# Adafruit_I2C_SPI_LCD_STEMMA_backpack.net
KiCad netlist of a schematic drawn in EAGLE
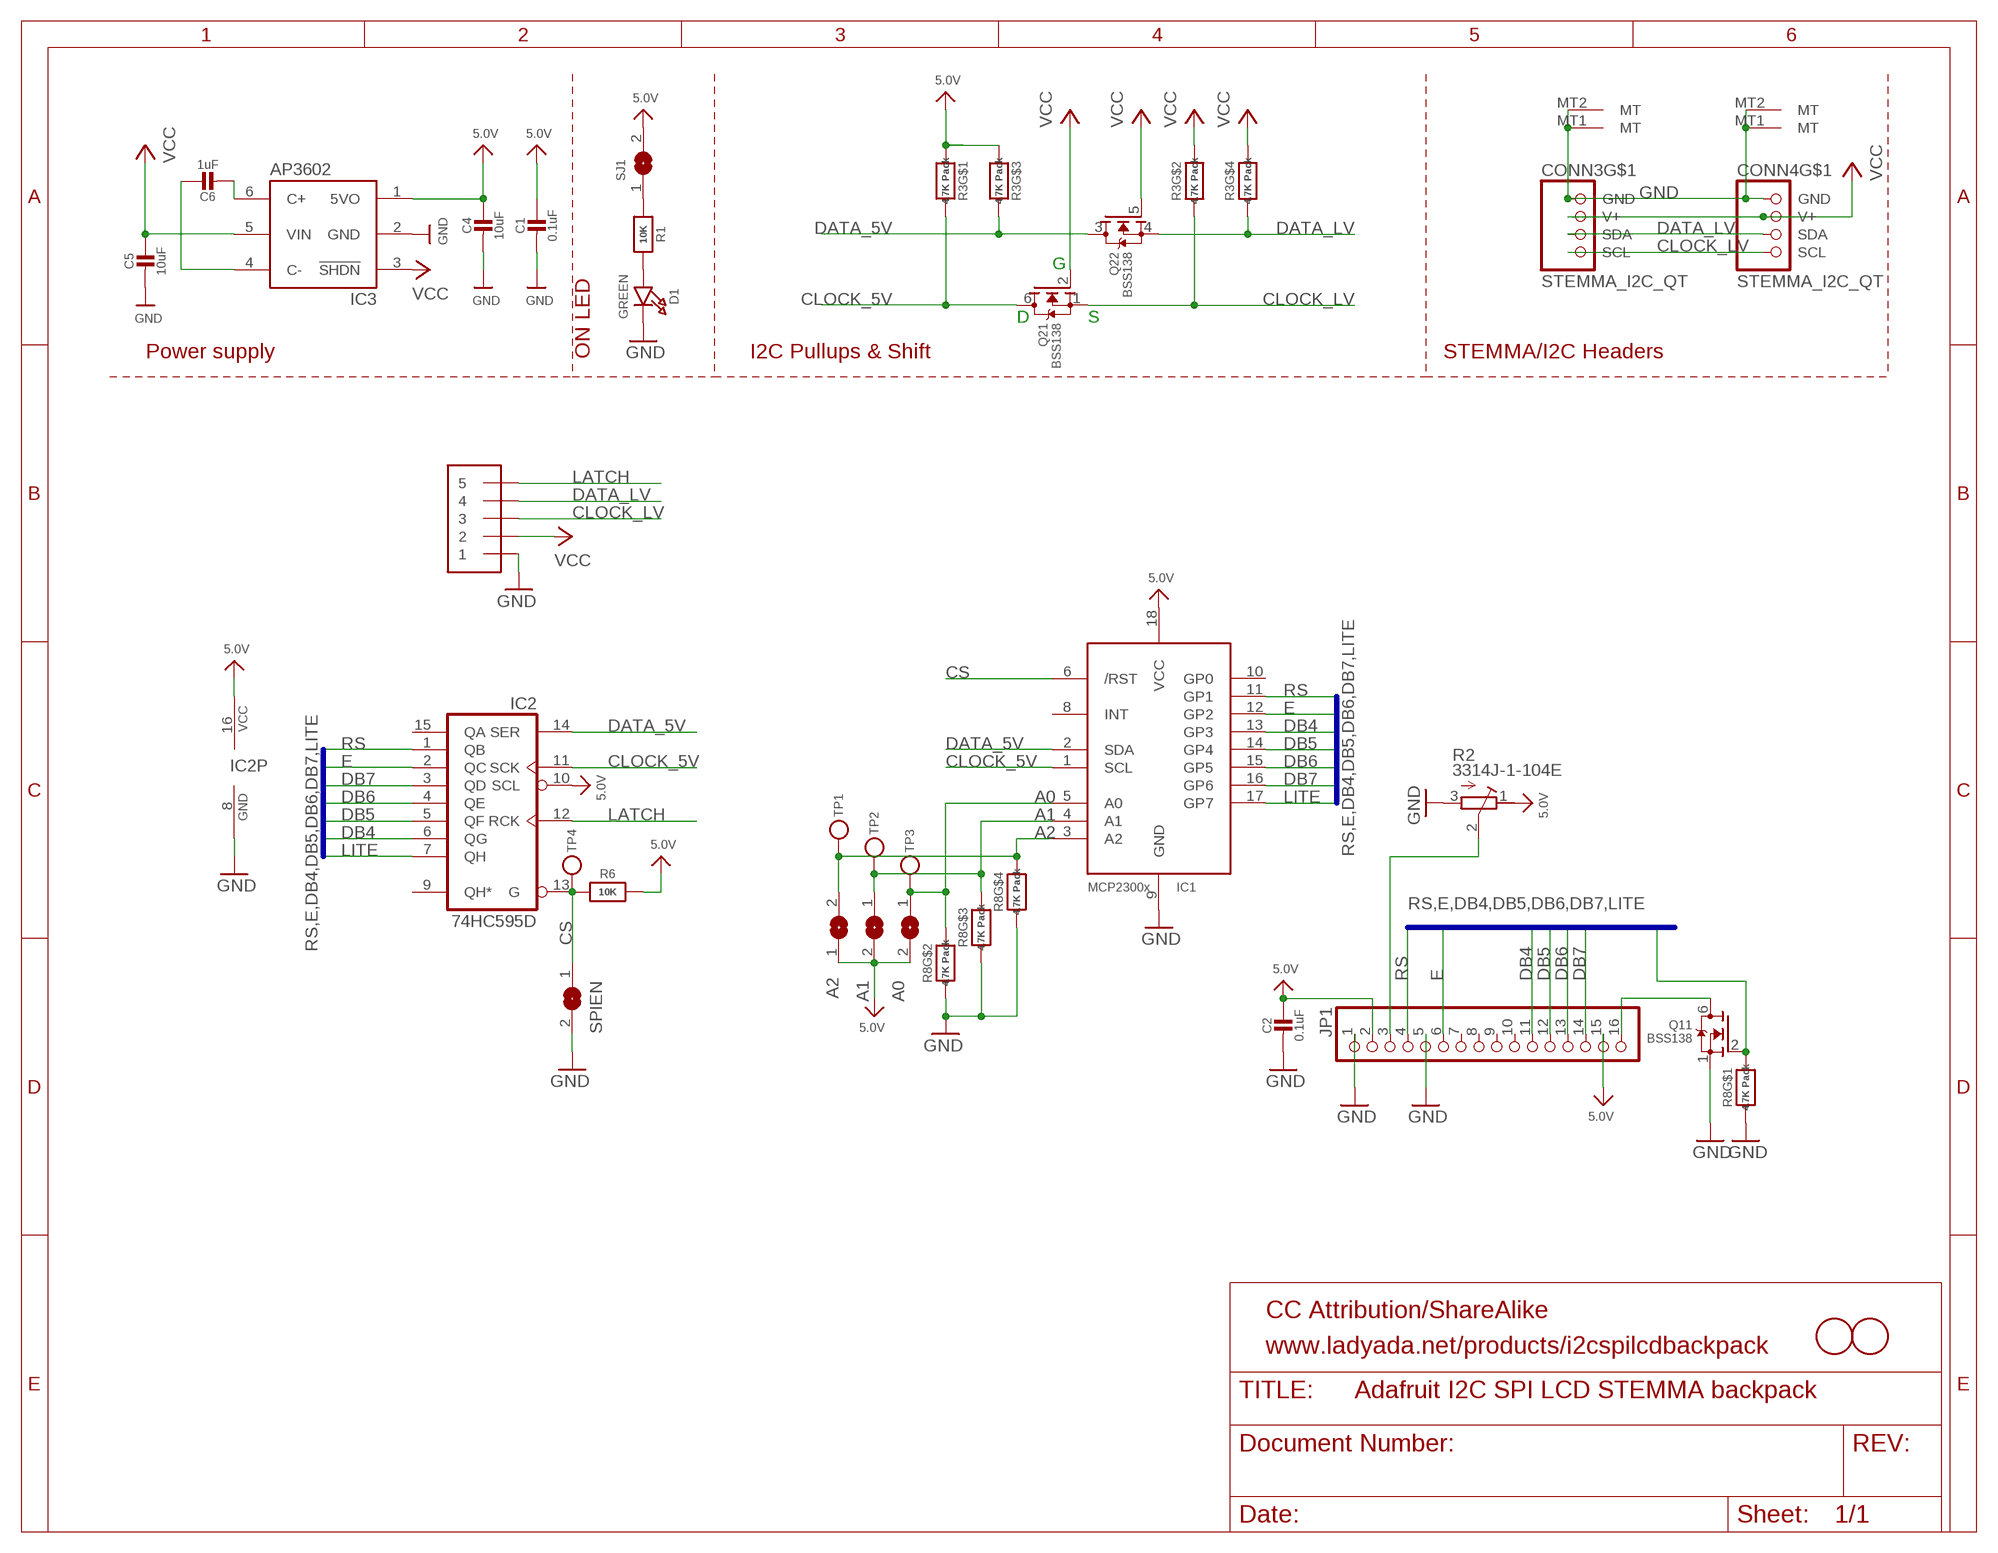
[diagram p0: schematic, sheet 1]

(export (version "E")
  (design (tool "Eeschema 10.0.6"))
  (components
    (comp (ref "A0")
      (value "SOLDERJUMPER")
      (footprint "eagle-import:SOLDERJUMPER_ARROW_NOPASTE")
      (libsource (lib "eagle-import") (part "SOLDERJUMPER"))
    )
    (comp (ref "A1")
      (value "SOLDERJUMPER")
      (footprint "eagle-import:SOLDERJUMPER_ARROW_NOPASTE")
      (libsource (lib "eagle-import") (part "SOLDERJUMPER"))
    )
    (comp (ref "A2")
      (value "SOLDERJUMPER")
      (footprint "eagle-import:SOLDERJUMPER_ARROW_NOPASTE")
      (libsource (lib "eagle-import") (part "SOLDERJUMPER"))
    )
    (comp (ref "C1")
      (value "0.1uF")
      (footprint "eagle-import:0603-NO")
      (libsource (lib "eagle-import") (part "CAP_CERAMIC0603_NO"))
    )
    (comp (ref "C2")
      (value "0.1uF")
      (footprint "eagle-import:0603-NO")
      (libsource (lib "eagle-import") (part "CAP_CERAMIC0603_NO"))
    )
    (comp (ref "C4")
      (value "10uF")
      (footprint "eagle-import:0805-NO")
      (libsource (lib "eagle-import") (part "CAP_CERAMIC0805-NOOUTLINE"))
    )
    (comp (ref "C5")
      (value "10uF")
      (footprint "eagle-import:0805-NO")
      (libsource (lib "eagle-import") (part "CAP_CERAMIC0805-NOOUTLINE"))
    )
    (comp (ref "C6")
      (value "1uF")
      (footprint "eagle-import:0805-NO")
      (libsource (lib "eagle-import") (part "CAP_CERAMIC0805-NOOUTLINE"))
    )
    (comp (ref "CONN3")
      (value "STEMMA_I2C_QT")
      (footprint "eagle-import:JST_SH4")
      (libsource (lib "eagle-import") (part "STEMMA_I2C_QT"))
    )
    (comp (ref "CONN4")
      (value "STEMMA_I2C_QT")
      (footprint "eagle-import:JST_SH4")
      (libsource (lib "eagle-import") (part "STEMMA_I2C_QT"))
    )
    (comp (ref "D1")
      (value "GREEN")
      (footprint "eagle-import:CHIPLED_0603_NOOUTLINE")
      (libsource (lib "eagle-import") (part "LED0603_NOOUTLINE"))
    )
    (comp (ref "IC1")
      (value "MCP23008/SO")
      (footprint "eagle-import:SO18W")
      (libsource (lib "eagle-import") (part "MCP23008/SO"))
    )
    (comp (ref "IC2")
      (value "74HC595D")
      (footprint "eagle-import:SO16")
      (libsource (lib "eagle-import") (part "74595DLS"))
    )
    (comp (ref "IC3")
      (value "AP3602/RT9361")
      (footprint "eagle-import:SOT23-6")
      (libsource (lib "eagle-import") (part "AP3602"))
    )
    (comp (ref "J1")
      (value "1X5")
      (footprint "eagle-import:1X05-3.5MM")
      (libsource (lib "eagle-import") (part "1X5"))
    )
    (comp (ref "JP1")
      (value "PINHD-1X16")
      (footprint "eagle-import:1X16")
      (libsource (lib "eagle-import") (part "PINHD-1X16"))
    )
    (comp (ref "Q1")
      (value "BSS138")
      (footprint "eagle-import:SOT363")
      (libsource (lib "eagle-import") (part "MOSFET-N_DUAL"))
    )
    (comp (ref "Q2")
      (value "BSS138")
      (footprint "eagle-import:SOT363")
      (libsource (lib "eagle-import") (part "MOSFET-N_DUAL"))
    )
    (comp (ref "R1")
      (value "10K")
      (footprint "eagle-import:0603-NO")
      (libsource (lib "eagle-import") (part "RESISTOR_0603_NOOUT"))
    )
    (comp (ref "R2")
      (value "3314J-1-104E")
      (footprint "eagle-import:RTRIM3314J")
      (libsource (lib "eagle-import") (part "R-TRIMM3314J"))
    )
    (comp (ref "R3")
      (value "4.7K Pack")
      (footprint "eagle-import:RESPACK_4X0603")
      (libsource (lib "eagle-import") (part "RESISTOR_4PACK"))
    )
    (comp (ref "R6")
      (value "10K")
      (footprint "eagle-import:0603-NO")
      (libsource (lib "eagle-import") (part "RESISTOR_0603_NOOUT"))
    )
    (comp (ref "R8")
      (value "4.7K Pack")
      (footprint "eagle-import:RESPACK_4X0603")
      (libsource (lib "eagle-import") (part "RESISTOR_4PACK"))
    )
    (comp (ref "SJ1")
      (value "SOLDERJUMPERCLOSED")
      (footprint "eagle-import:SOLDERJUMPER_CLOSEDWIRE")
      (libsource (lib "eagle-import") (part "SOLDERJUMPERCLOSED"))
    )
    (comp (ref "SPIEN")
      (value "SOLDERJUMPER")
      (footprint "eagle-import:SOLDERJUMPER_ARROW_NOPASTE")
      (libsource (lib "eagle-import") (part "SOLDERJUMPER"))
    )
    (comp (ref "TP1")
      (value "TESTPOINTROUND1.5MM")
      (footprint "eagle-import:TESTPOINT_ROUND_1.5MM")
      (libsource (lib "eagle-import") (part "TESTPOINTROUND1.5MM"))
    )
    (comp (ref "TP2")
      (value "TESTPOINTROUND1.5MM")
      (footprint "eagle-import:TESTPOINT_ROUND_1.5MM")
      (libsource (lib "eagle-import") (part "TESTPOINTROUND1.5MM"))
    )
    (comp (ref "TP3")
      (value "TESTPOINTROUND1.5MM")
      (footprint "eagle-import:TESTPOINT_ROUND_1.5MM")
      (libsource (lib "eagle-import") (part "TESTPOINTROUND1.5MM"))
    )
    (comp (ref "TP4")
      (value "TESTPOINTROUND1.5MM")
      (footprint "eagle-import:TESTPOINT_ROUND_1.5MM")
      (libsource (lib "eagle-import") (part "TESTPOINTROUND1.5MM"))
    )
    (comp (ref "U$1")
      (value "FIDUCIAL")
      (footprint "eagle-import:FIDUCIAL_1MM")
      (libsource (lib "eagle-import") (part "FIDUCIAL"))
    )
    (comp (ref "U$2")
      (value "FIDUCIAL")
      (footprint "eagle-import:FIDUCIAL_1MM")
      (libsource (lib "eagle-import") (part "FIDUCIAL"))
    )
  )
  (nets
    (net (code "1") (name "/A0") (class "Default")
      (node (ref "A0") (pin "1") (pinfunction "1_1") (pintype "passive"))
      (node (ref "IC1") (pin "5") (pinfunction "A0_5") (pintype "input"))
      (node (ref "R8") (pin "7") (pinfunction "2_7") (pintype "passive"))
      (node (ref "TP3") (pin "P$1") (pinfunction "P$1_P$1") (pintype "bidirectional"))
    )
    (net (code "2") (name "/A1") (class "Default")
      (node (ref "A1") (pin "1") (pinfunction "1_1") (pintype "passive"))
      (node (ref "IC1") (pin "4") (pinfunction "A1_4") (pintype "input"))
      (node (ref "R8") (pin "6") (pinfunction "2_6") (pintype "passive"))
      (node (ref "TP2") (pin "P$1") (pinfunction "P$1_P$1") (pintype "bidirectional"))
    )
    (net (code "3") (name "/A2") (class "Default")
      (node (ref "A2") (pin "2") (pinfunction "2_2") (pintype "passive"))
      (node (ref "IC1") (pin "3") (pinfunction "A2_3") (pintype "input"))
      (node (ref "R8") (pin "5") (pinfunction "2_5") (pintype "passive"))
      (node (ref "TP1") (pin "P$1") (pinfunction "P$1_P$1") (pintype "bidirectional"))
    )
    (net (code "4") (name "/CLOCK_5V") (class "Default")
      (node (ref "IC1") (pin "1") (pinfunction "SCL_1") (pintype "bidirectional"))
      (node (ref "IC2") (pin "11") (pinfunction "SCK_11") (pintype "input"))
      (node (ref "Q2") (pin "6") (pinfunction "D_6") (pintype "bidirectional"))
      (node (ref "R3") (pin "8") (pinfunction "2_8") (pintype "passive"))
    )
    (net (code "5") (name "/CLOCK_LV") (class "Default")
      (node (ref "CONN3") (pin "4") (pinfunction "SCL_4") (pintype "passive"))
      (node (ref "CONN4") (pin "4") (pinfunction "SCL_4") (pintype "passive"))
      (node (ref "J1") (pin "3") (pinfunction "3_3") (pintype "passive"))
      (node (ref "Q2") (pin "1") (pinfunction "S_1") (pintype "bidirectional"))
      (node (ref "R3") (pin "7") (pinfunction "2_7") (pintype "passive"))
    )
    (net (code "6") (name "/CS") (class "Default")
      (node (ref "IC1") (pin "6") (pinfunction "/RST_6") (pintype "input"))
      (node (ref "IC2") (pin "13") (pinfunction "G_13") (pintype "input"))
      (node (ref "R6") (pin "2") (pinfunction "2_2") (pintype "passive"))
      (node (ref "SPIEN") (pin "1") (pinfunction "1_1") (pintype "passive"))
      (node (ref "TP4") (pin "P$1") (pinfunction "P$1_P$1") (pintype "bidirectional"))
    )
    (net (code "7") (name "/DATA_5V") (class "Default")
      (node (ref "IC1") (pin "2") (pinfunction "SDA_2") (pintype "bidirectional"))
      (node (ref "IC2") (pin "14") (pinfunction "SER_14") (pintype "input"))
      (node (ref "Q2") (pin "3") (pinfunction "D_3") (pintype "bidirectional"))
      (node (ref "R3") (pin "6") (pinfunction "2_6") (pintype "passive"))
    )
    (net (code "8") (name "/DATA_LV") (class "Default")
      (node (ref "CONN3") (pin "3") (pinfunction "SDA_3") (pintype "passive"))
      (node (ref "CONN4") (pin "3") (pinfunction "SDA_3") (pintype "passive"))
      (node (ref "J1") (pin "4") (pinfunction "4_4") (pintype "passive"))
      (node (ref "Q2") (pin "4") (pinfunction "S_4") (pintype "bidirectional"))
      (node (ref "R3") (pin "5") (pinfunction "2_5") (pintype "passive"))
    )
    (net (code "9") (name "/DB4") (class "Default")
      (node (ref "IC1") (pin "13") (pinfunction "GP3_13") (pintype "bidirectional"))
      (node (ref "IC2") (pin "6") (pinfunction "QG_6") (pintype "tri_state"))
      (node (ref "JP1") (pin "11") (pinfunction "11_11") (pintype "passive"))
    )
    (net (code "10") (name "/DB5") (class "Default")
      (node (ref "IC1") (pin "14") (pinfunction "GP4_14") (pintype "bidirectional"))
      (node (ref "IC2") (pin "5") (pinfunction "QF_5") (pintype "tri_state"))
      (node (ref "JP1") (pin "12") (pinfunction "12_12") (pintype "passive"))
    )
    (net (code "11") (name "/DB6") (class "Default")
      (node (ref "IC1") (pin "15") (pinfunction "GP5_15") (pintype "bidirectional"))
      (node (ref "IC2") (pin "4") (pinfunction "QE_4") (pintype "tri_state"))
      (node (ref "JP1") (pin "13") (pinfunction "13_13") (pintype "passive"))
    )
    (net (code "12") (name "/DB7") (class "Default")
      (node (ref "IC1") (pin "16") (pinfunction "GP6_16") (pintype "bidirectional"))
      (node (ref "IC2") (pin "3") (pinfunction "QD_3") (pintype "tri_state"))
      (node (ref "JP1") (pin "14") (pinfunction "14_14") (pintype "passive"))
    )
    (net (code "13") (name "/E") (class "Default")
      (node (ref "IC1") (pin "12") (pinfunction "GP2_12") (pintype "bidirectional"))
      (node (ref "IC2") (pin "2") (pinfunction "QC_2") (pintype "tri_state"))
      (node (ref "JP1") (pin "6") (pinfunction "6_6") (pintype "passive"))
    )
    (net (code "14") (name "/LATCH") (class "Default")
      (node (ref "IC2") (pin "12") (pinfunction "RCK_12") (pintype "input"))
      (node (ref "J1") (pin "5") (pinfunction "5_5") (pintype "passive"))
    )
    (net (code "15") (name "/LITE") (class "Default")
      (node (ref "IC1") (pin "17") (pinfunction "GP7_17") (pintype "bidirectional"))
      (node (ref "IC2") (pin "7") (pinfunction "QH_7") (pintype "tri_state"))
      (node (ref "Q1") (pin "2") (pinfunction "G_2") (pintype "bidirectional"))
      (node (ref "R8") (pin "8") (pinfunction "2_8") (pintype "passive"))
    )
    (net (code "16") (name "/RS") (class "Default")
      (node (ref "IC1") (pin "11") (pinfunction "GP1_11") (pintype "bidirectional"))
      (node (ref "IC2") (pin "1") (pinfunction "QB_1") (pintype "tri_state"))
      (node (ref "JP1") (pin "4") (pinfunction "4_4") (pintype "passive"))
    )
    (net (code "18") (name "5.0V") (class "Default")
      (node (ref "A0") (pin "2") (pinfunction "2_2") (pintype "passive"))
      (node (ref "A1") (pin "2") (pinfunction "2_2") (pintype "passive"))
      (node (ref "A2") (pin "1") (pinfunction "1_1") (pintype "passive"))
      (node (ref "C1") (pin "1") (pinfunction "1_1") (pintype "passive"))
      (node (ref "C2") (pin "1") (pinfunction "1_1") (pintype "passive"))
      (node (ref "C4") (pin "1") (pinfunction "1_1") (pintype "passive"))
      (node (ref "IC1") (pin "18") (pinfunction "VCC_18") (pintype "power_in"))
      (node (ref "IC2") (pin "10") (pinfunction "SCL_10") (pintype "input"))
      (node (ref "IC2") (pin "16") (pinfunction "VCC_16") (pintype "power_in"))
      (node (ref "IC3") (pin "1") (pinfunction "5VO_1") (pintype "power_in"))
      (node (ref "JP1") (pin "15") (pinfunction "15_15") (pintype "passive"))
      (node (ref "JP1") (pin "2") (pinfunction "2_2") (pintype "passive"))
      (node (ref "R2") (pin "1") (pinfunction "E_1") (pintype "passive"))
      (node (ref "R3") (pin "1") (pinfunction "1_1") (pintype "passive"))
      (node (ref "R3") (pin "3") (pinfunction "1_3") (pintype "passive"))
      (node (ref "R6") (pin "1") (pinfunction "1_1") (pintype "passive"))
      (node (ref "SJ1") (pin "2") (pinfunction "2_2") (pintype "passive"))
    )
    (net (code "19") (name "GND") (class "Default")
      (node (ref "C1") (pin "2") (pinfunction "2_2") (pintype "passive"))
      (node (ref "C2") (pin "2") (pinfunction "2_2") (pintype "passive"))
      (node (ref "C4") (pin "2") (pinfunction "2_2") (pintype "passive"))
      (node (ref "C5") (pin "2") (pinfunction "2_2") (pintype "passive"))
      (node (ref "CONN3") (pin "1") (pinfunction "GND_1") (pintype "passive"))
      (node (ref "CONN3") (pin "MT1") (pinfunction "MT_MT1") (pintype "bidirectional"))
      (node (ref "CONN3") (pin "MT2") (pinfunction "MT_MT2") (pintype "bidirectional"))
      (node (ref "CONN4") (pin "1") (pinfunction "GND_1") (pintype "passive"))
      (node (ref "CONN4") (pin "MT1") (pinfunction "MT_MT1") (pintype "bidirectional"))
      (node (ref "CONN4") (pin "MT2") (pinfunction "MT_MT2") (pintype "bidirectional"))
      (node (ref "D1") (pin "C") (pinfunction "C_C") (pintype "passive"))
      (node (ref "IC1") (pin "9") (pinfunction "GND_9") (pintype "power_in"))
      (node (ref "IC2") (pin "8") (pinfunction "GND_8") (pintype "power_in"))
      (node (ref "IC3") (pin "2") (pinfunction "GND_2") (pintype "power_in"))
      (node (ref "J1") (pin "1") (pinfunction "1_1") (pintype "passive"))
      (node (ref "JP1") (pin "1") (pinfunction "1_1") (pintype "passive"))
      (node (ref "JP1") (pin "5") (pinfunction "5_5") (pintype "passive"))
      (node (ref "Q1") (pin "1") (pinfunction "S_1") (pintype "bidirectional"))
      (node (ref "R2") (pin "3") (pinfunction "A_3") (pintype "passive"))
      (node (ref "R8") (pin "1") (pinfunction "1_1") (pintype "passive"))
      (node (ref "R8") (pin "2") (pinfunction "1_2") (pintype "passive"))
      (node (ref "R8") (pin "3") (pinfunction "1_3") (pintype "passive"))
      (node (ref "R8") (pin "4") (pinfunction "1_4") (pintype "passive"))
      (node (ref "SPIEN") (pin "2") (pinfunction "2_2") (pintype "passive"))
    )
    (net (code "20") (name "Net-(D1-PadA)") (class "Default")
      (node (ref "D1") (pin "A") (pinfunction "A_A") (pintype "passive"))
      (node (ref "R1") (pin "2") (pinfunction "2_2") (pintype "passive"))
    )
    (net (code "21") (name "Net-(IC3-C+)") (class "Default")
      (node (ref "C6") (pin "2") (pinfunction "2_2") (pintype "passive"))
      (node (ref "IC3") (pin "6") (pinfunction "C+_6") (pintype "bidirectional"))
    )
    (net (code "22") (name "Net-(IC3-C-)") (class "Default")
      (node (ref "C6") (pin "1") (pinfunction "1_1") (pintype "passive"))
      (node (ref "IC3") (pin "4") (pinfunction "C-_4") (pintype "bidirectional"))
    )
    (net (code "23") (name "Net-(Q1A-D)") (class "Default")
      (node (ref "JP1") (pin "16") (pinfunction "16_16") (pintype "passive"))
      (node (ref "Q1") (pin "6") (pinfunction "D_6") (pintype "bidirectional"))
    )
    (net (code "24") (name "Net-(R1-Pad1)") (class "Default")
      (node (ref "R1") (pin "1") (pinfunction "1_1") (pintype "passive"))
      (node (ref "SJ1") (pin "1") (pinfunction "1_1") (pintype "passive"))
    )
    (net (code "25") (name "Net-(R2-S)") (class "Default")
      (node (ref "JP1") (pin "3") (pinfunction "3_3") (pintype "passive"))
      (node (ref "R2") (pin "2") (pinfunction "S_2") (pintype "passive"))
    )
    (net (code "26") (name "VCC") (class "Default")
      (node (ref "C5") (pin "1") (pinfunction "1_1") (pintype "passive"))
      (node (ref "CONN3") (pin "2") (pinfunction "V+_2") (pintype "passive"))
      (node (ref "CONN4") (pin "2") (pinfunction "V+_2") (pintype "passive"))
      (node (ref "IC3") (pin "3") (pinfunction "~{SHDN}_3") (pintype "input"))
      (node (ref "IC3") (pin "5") (pinfunction "VIN_5") (pintype "power_in"))
      (node (ref "J1") (pin "2") (pinfunction "2_2") (pintype "passive"))
      (node (ref "Q2") (pin "2") (pinfunction "G_2") (pintype "bidirectional"))
      (node (ref "Q2") (pin "5") (pinfunction "G_5") (pintype "bidirectional"))
      (node (ref "R3") (pin "2") (pinfunction "1_2") (pintype "passive"))
      (node (ref "R3") (pin "4") (pinfunction "1_4") (pintype "passive"))
    )
    (net (code "27") (name "unconnected-(IC1-GP0-Pad10)") (class "Default")
      (node (ref "IC1") (pin "10") (pinfunction "GP0_10") (pintype "bidirectional"))
    )
    (net (code "28") (name "unconnected-(IC1-INT-Pad8)") (class "Default")
      (node (ref "IC1") (pin "8") (pinfunction "INT_8") (pintype "output"))
    )
    (net (code "29") (name "unconnected-(IC2A-QA-Pad15)") (class "Default")
      (node (ref "IC2") (pin "15") (pinfunction "QA_15") (pintype "tri_state"))
    )
    (net (code "30") (name "unconnected-(IC2A-QH*-Pad9)") (class "Default")
      (node (ref "IC2") (pin "9") (pinfunction "QH*_9") (pintype "tri_state"))
    )
    (net (code "31") (name "unconnected-(JP1-Pad7)") (class "Default")
      (node (ref "JP1") (pin "7") (pinfunction "7_7") (pintype "passive"))
    )
    (net (code "32") (name "unconnected-(JP1-Pad8)") (class "Default")
      (node (ref "JP1") (pin "8") (pinfunction "8_8") (pintype "passive"))
    )
    (net (code "33") (name "unconnected-(JP1-Pad9)") (class "Default")
      (node (ref "JP1") (pin "9") (pinfunction "9_9") (pintype "passive"))
    )
    (net (code "34") (name "unconnected-(JP1-Pad10)") (class "Default")
      (node (ref "JP1") (pin "10") (pinfunction "10_10") (pintype "passive"))
    )
  )
)
